# Sheet1.net
KiCad netlist of a schematic drawn in Altium Designer
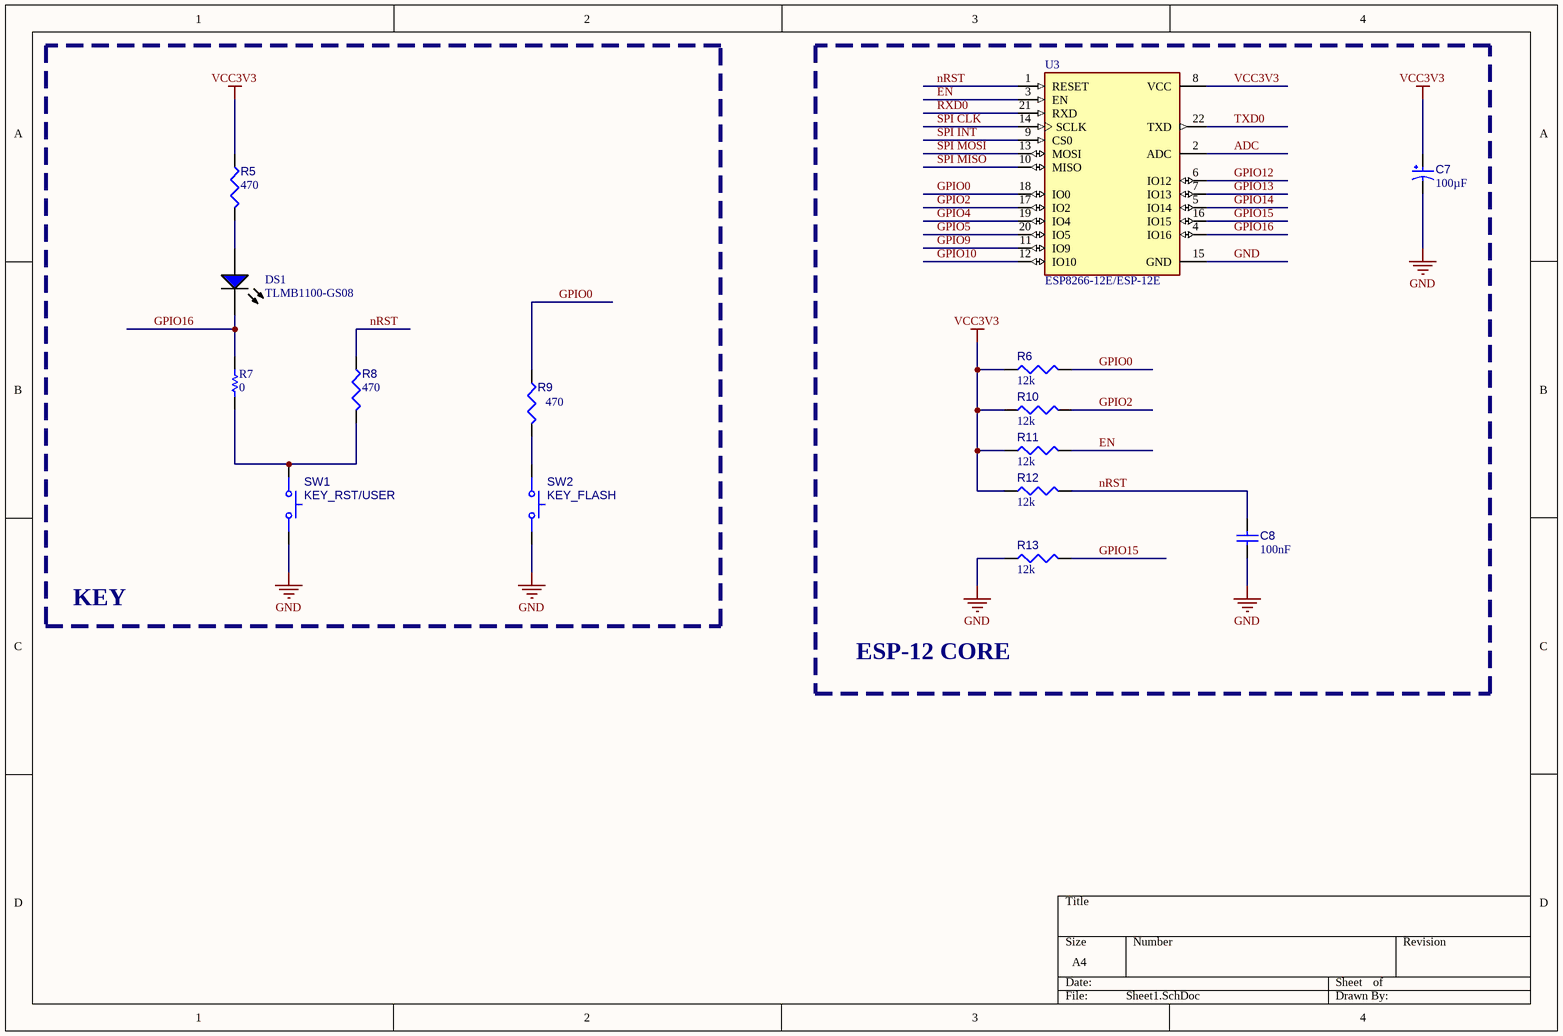
[diagram p0: Sheet1.SchDoc]

(export (version "E")
  (design (tool "Eeschema 10.0.6"))
  (components
    (comp (ref "C7")
      (value "100µF")
      (footprint "AVX-TAJ-C-2_M")
      (description "Standard Tantalum, 100 uF, +/- 10%, 16 V, -55 to 125 degC, 2312 (6032 Metric), RoHS, Tape and Reel")
      (fields (field (name "TOLERANCE") "10%") (field (name "MANUFACTURER") "AVX"))
      (libsource (lib "Vasavi College of Engineering-Educator Program") (part "CAP-P-2"))
    )
    (comp (ref "C8")
      (value "100nF")
      (footprint "CAPC2013X95X50LL10T25")
      (description "Chip Capacitor, 100 nF, +/- 10%, 50 V, 0805 (2012 Metric)")
      (fields (field (name "TOLERANCE") "10%") (field (name "Comment") "Capacitor 100 nF +/-10% 50 V 0805"))
      (libsource (lib "Vasavi College of Engineering-Educator Program") (part "CAP-NP-2"))
    )
    (comp (ref "DS1")
      (value "TLMB1100-GS08")
      (footprint "VISH-TLMX1100-2_V")
      (description "Blue LED, 10 mA, 3.9 V, -40 to 100 degC, 2-Pin SMD (0603), RoHS, Tape and Reel")
      (fields (field (name "POWER") "68mW") (field (name "MANUFACTURER") "Vishay Semiconductor"))
      (libsource (lib "Vasavi College of Engineering-Educator Program") (part "LED-BLUE-AK-2"))
    )
    (comp (ref "R5")
      (value "470")
      (footprint "RESC0805(2012)_L")
      (description "Chip Resistor, 470 Ohms, +/-5%, 125 mW, -55 to 155 degC, 0805")
      (fields (field (name "TOLERANCE") "5%") (field (name "POWER") "125mW"))
      (libsource (lib "Vasavi College of Engineering-Educator Program") (part "RES-2"))
    )
    (comp (ref "R6")
      (value "12k")
      (footprint "RESC0402(1005)_L")
      (description "Chip Resistor, 12 kOhms, +/-1 %, 63 mW, -55 to 155 degC, 0402")
      (fields (field (name "POWER") "63mW") (field (name "TOLERANCE") "1%"))
      (libsource (lib "Vasavi College of Engineering-Educator Program") (part "RES-2"))
    )
    (comp (ref "R7")
      (value "0")
      (footprint "RESC1608X55X25ML10T15")
      (description "Chip Resistor, 0 Ohm, 0.1 W, -55 to 155 degC, 0603 (1608 Metric)")
      (fields (field (name "POWER") "100mW") (field (name "TOLERANCE") "5%"))
      (libsource (lib "") (part "RES-2_1"))
    )
    (comp (ref "R8")
      (value "470")
      (footprint "RESC0805(2012)_L")
      (description "Chip Resistor, 470 Ohms, +/-5%, 125 mW, -55 to 155 degC, 0805")
      (fields (field (name "TOLERANCE") "5%") (field (name "POWER") "125mW"))
      (libsource (lib "Vasavi College of Engineering-Educator Program") (part "RES-2"))
    )
    (comp (ref "R9")
      (value "470")
      (footprint "RESC0805(2012)_L")
      (description "Chip Resistor, 470 Ohms, +/-5%, 125 mW, -55 to 155 degC, 0805")
      (fields (field (name "TOLERANCE") "5%") (field (name "POWER") "125mW"))
      (libsource (lib "Vasavi College of Engineering-Educator Program") (part "RES-2"))
    )
    (comp (ref "R10")
      (value "12k")
      (footprint "RESC0402(1005)_L")
      (description "Chip Resistor, 12 kOhms, +/-1 %, 63 mW, -55 to 155 degC, 0402")
      (fields (field (name "POWER") "63mW") (field (name "TOLERANCE") "1%"))
      (libsource (lib "Vasavi College of Engineering-Educator Program") (part "RES-2"))
    )
    (comp (ref "R11")
      (value "12k")
      (footprint "RESC0402(1005)_L")
      (description "Chip Resistor, 12 kOhms, +/-1 %, 63 mW, -55 to 155 degC, 0402")
      (fields (field (name "POWER") "63mW") (field (name "TOLERANCE") "1%"))
      (libsource (lib "Vasavi College of Engineering-Educator Program") (part "RES-2"))
    )
    (comp (ref "R12")
      (value "12k")
      (footprint "RESC0402(1005)_L")
      (description "Chip Resistor, 12 kOhms, +/-1 %, 63 mW, -55 to 155 degC, 0402")
      (fields (field (name "POWER") "63mW") (field (name "TOLERANCE") "1%"))
      (libsource (lib "Vasavi College of Engineering-Educator Program") (part "RES-2"))
    )
    (comp (ref "R13")
      (value "12k")
      (footprint "RESC0402(1005)_L")
      (description "Chip Resistor, 12 kOhms, +/-1 %, 63 mW, -55 to 155 degC, 0402")
      (fields (field (name "POWER") "63mW") (field (name "TOLERANCE") "1%"))
      (libsource (lib "Vasavi College of Engineering-Educator Program") (part "RES-2"))
    )
    (comp (ref "SW1")
      (value "KEY_RST/USER")
      (footprint "OMRON-B3U-1000P-2-B_V")
      (libsource (lib "Vasavi College of Engineering-Educator Program") (part "CMP-00164-6"))
    )
    (comp (ref "SW2")
      (value "KEY_FLASH")
      (footprint "OMRON-B3U-1000P-2-B_V")
      (libsource (lib "Vasavi College of Engineering-Educator Program") (part "CMP-00164-6"))
    )
    (comp (ref "U3")
      (value "ESP8266-12E/ESP-12E")
      (footprint "XCVR_ESP8266-12E/ESP-12E")
      (fields (field (name "MF") "AI-Thinker"))
      (libsource (lib "Vasavi College of Engineering-Educator Program") (part "ESP8266-12E/ESP-12E"))
    )
  )
  (nets
    (net (code "1") (name "/ADC") (class "Default")
      (node (ref "U3") (pin "2") (pinfunction "ADC_2") (pintype "passive"))
    )
    (net (code "2") (name "/EN") (class "Default")
      (node (ref "R11") (pin "2") (pinfunction "2_2") (pintype "passive"))
      (node (ref "U3") (pin "3") (pinfunction "EN_3") (pintype "input"))
    )
    (net (code "3") (name "/GPIO0") (class "Default")
      (node (ref "R6") (pin "2") (pinfunction "2_2") (pintype "passive"))
      (node (ref "R9") (pin "1") (pinfunction "1_1") (pintype "passive"))
      (node (ref "U3") (pin "18") (pinfunction "IO0_18") (pintype "bidirectional"))
    )
    (net (code "4") (name "/GPIO2") (class "Default")
      (node (ref "R10") (pin "2") (pinfunction "2_2") (pintype "passive"))
      (node (ref "U3") (pin "17") (pinfunction "IO2_17") (pintype "bidirectional"))
    )
    (net (code "5") (name "/GPIO4") (class "Default")
      (node (ref "U3") (pin "19") (pinfunction "IO4_19") (pintype "bidirectional"))
    )
    (net (code "6") (name "/GPIO5") (class "Default")
      (node (ref "U3") (pin "20") (pinfunction "IO5_20") (pintype "bidirectional"))
    )
    (net (code "7") (name "/GPIO9") (class "Default")
      (node (ref "U3") (pin "11") (pinfunction "IO9_11") (pintype "bidirectional"))
    )
    (net (code "8") (name "/GPIO10") (class "Default")
      (node (ref "U3") (pin "12") (pinfunction "IO10_12") (pintype "bidirectional"))
    )
    (net (code "9") (name "/GPIO12") (class "Default")
      (node (ref "U3") (pin "6") (pinfunction "IO12_6") (pintype "bidirectional"))
    )
    (net (code "10") (name "/GPIO13") (class "Default")
      (node (ref "U3") (pin "7") (pinfunction "IO13_7") (pintype "bidirectional"))
    )
    (net (code "11") (name "/GPIO14") (class "Default")
      (node (ref "U3") (pin "5") (pinfunction "IO14_5") (pintype "bidirectional"))
    )
    (net (code "12") (name "/GPIO15") (class "Default")
      (node (ref "R13") (pin "2") (pinfunction "2_2") (pintype "passive"))
      (node (ref "U3") (pin "16") (pinfunction "IO15_16") (pintype "bidirectional"))
    )
    (net (code "13") (name "/GPIO16") (class "Default")
      (node (ref "DS1") (pin "2") (pinfunction "K_2") (pintype "passive"))
      (node (ref "R7") (pin "1") (pinfunction "1_1") (pintype "passive"))
      (node (ref "U3") (pin "4") (pinfunction "IO16_4") (pintype "bidirectional"))
    )
    (net (code "14") (name "/RXD0") (class "Default")
      (node (ref "U3") (pin "21") (pinfunction "RXD_21") (pintype "input"))
    )
    (net (code "15") (name "/SPI CLK") (class "Default")
      (node (ref "U3") (pin "14") (pinfunction "SCLK_14") (pintype "input"))
    )
    (net (code "16") (name "/SPI INT") (class "Default")
      (node (ref "U3") (pin "9") (pinfunction "CS0_9") (pintype "input"))
    )
    (net (code "17") (name "/SPI MISO") (class "Default")
      (node (ref "U3") (pin "10") (pinfunction "MISO_10") (pintype "bidirectional"))
    )
    (net (code "18") (name "/SPI MOSI") (class "Default")
      (node (ref "U3") (pin "13") (pinfunction "MOSI_13") (pintype "bidirectional"))
    )
    (net (code "19") (name "/TXD0") (class "Default")
      (node (ref "U3") (pin "22") (pinfunction "TXD_22") (pintype "output"))
    )
    (net (code "20") (name "/nRST") (class "Default")
      (node (ref "C8") (pin "1") (pinfunction "1_1") (pintype "passive"))
      (node (ref "R12") (pin "2") (pinfunction "2_2") (pintype "passive"))
      (node (ref "R8") (pin "1") (pinfunction "1_1") (pintype "passive"))
      (node (ref "U3") (pin "1") (pinfunction "RESET_1") (pintype "input"))
    )
    (net (code "21") (name "GND") (class "Default")
      (node (ref "C7") (pin "2") (pinfunction "2_2") (pintype "passive"))
      (node (ref "C8") (pin "2") (pinfunction "2_2") (pintype "passive"))
      (node (ref "R13") (pin "1") (pinfunction "1_1") (pintype "passive"))
      (node (ref "SW1") (pin "2") (pinfunction "2_2") (pintype "passive"))
      (node (ref "SW2") (pin "2") (pinfunction "2_2") (pintype "passive"))
      (node (ref "U3") (pin "15") (pinfunction "GND_15") (pintype "power_in"))
    )
    (net (code "22") (name "Net-(DS1-A)") (class "Default")
      (node (ref "DS1") (pin "1") (pinfunction "A_1") (pintype "passive"))
      (node (ref "R5") (pin "2") (pinfunction "2_2") (pintype "passive"))
    )
    (net (code "23") (name "Net-(R7-Pad2)") (class "Default")
      (node (ref "R7") (pin "2") (pinfunction "2_2") (pintype "passive"))
      (node (ref "R8") (pin "2") (pinfunction "2_2") (pintype "passive"))
      (node (ref "SW1") (pin "1") (pinfunction "1_1") (pintype "passive"))
    )
    (net (code "24") (name "Net-(R9-Pad2)") (class "Default")
      (node (ref "R9") (pin "2") (pinfunction "2_2") (pintype "passive"))
      (node (ref "SW2") (pin "1") (pinfunction "1_1") (pintype "passive"))
    )
    (net (code "25") (name "VCC3V3") (class "Default")
      (node (ref "C7") (pin "1") (pinfunction "1_1") (pintype "passive"))
      (node (ref "R10") (pin "1") (pinfunction "1_1") (pintype "passive"))
      (node (ref "R11") (pin "1") (pinfunction "1_1") (pintype "passive"))
      (node (ref "R12") (pin "1") (pinfunction "1_1") (pintype "passive"))
      (node (ref "R5") (pin "1") (pinfunction "1_1") (pintype "passive"))
      (node (ref "R6") (pin "1") (pinfunction "1_1") (pintype "passive"))
      (node (ref "U3") (pin "8") (pinfunction "VCC_8") (pintype "power_in"))
    )
  )
)
